# New_Multirotor_GPS_V1_2.net
KiCad netlist of a schematic drawn in EAGLE
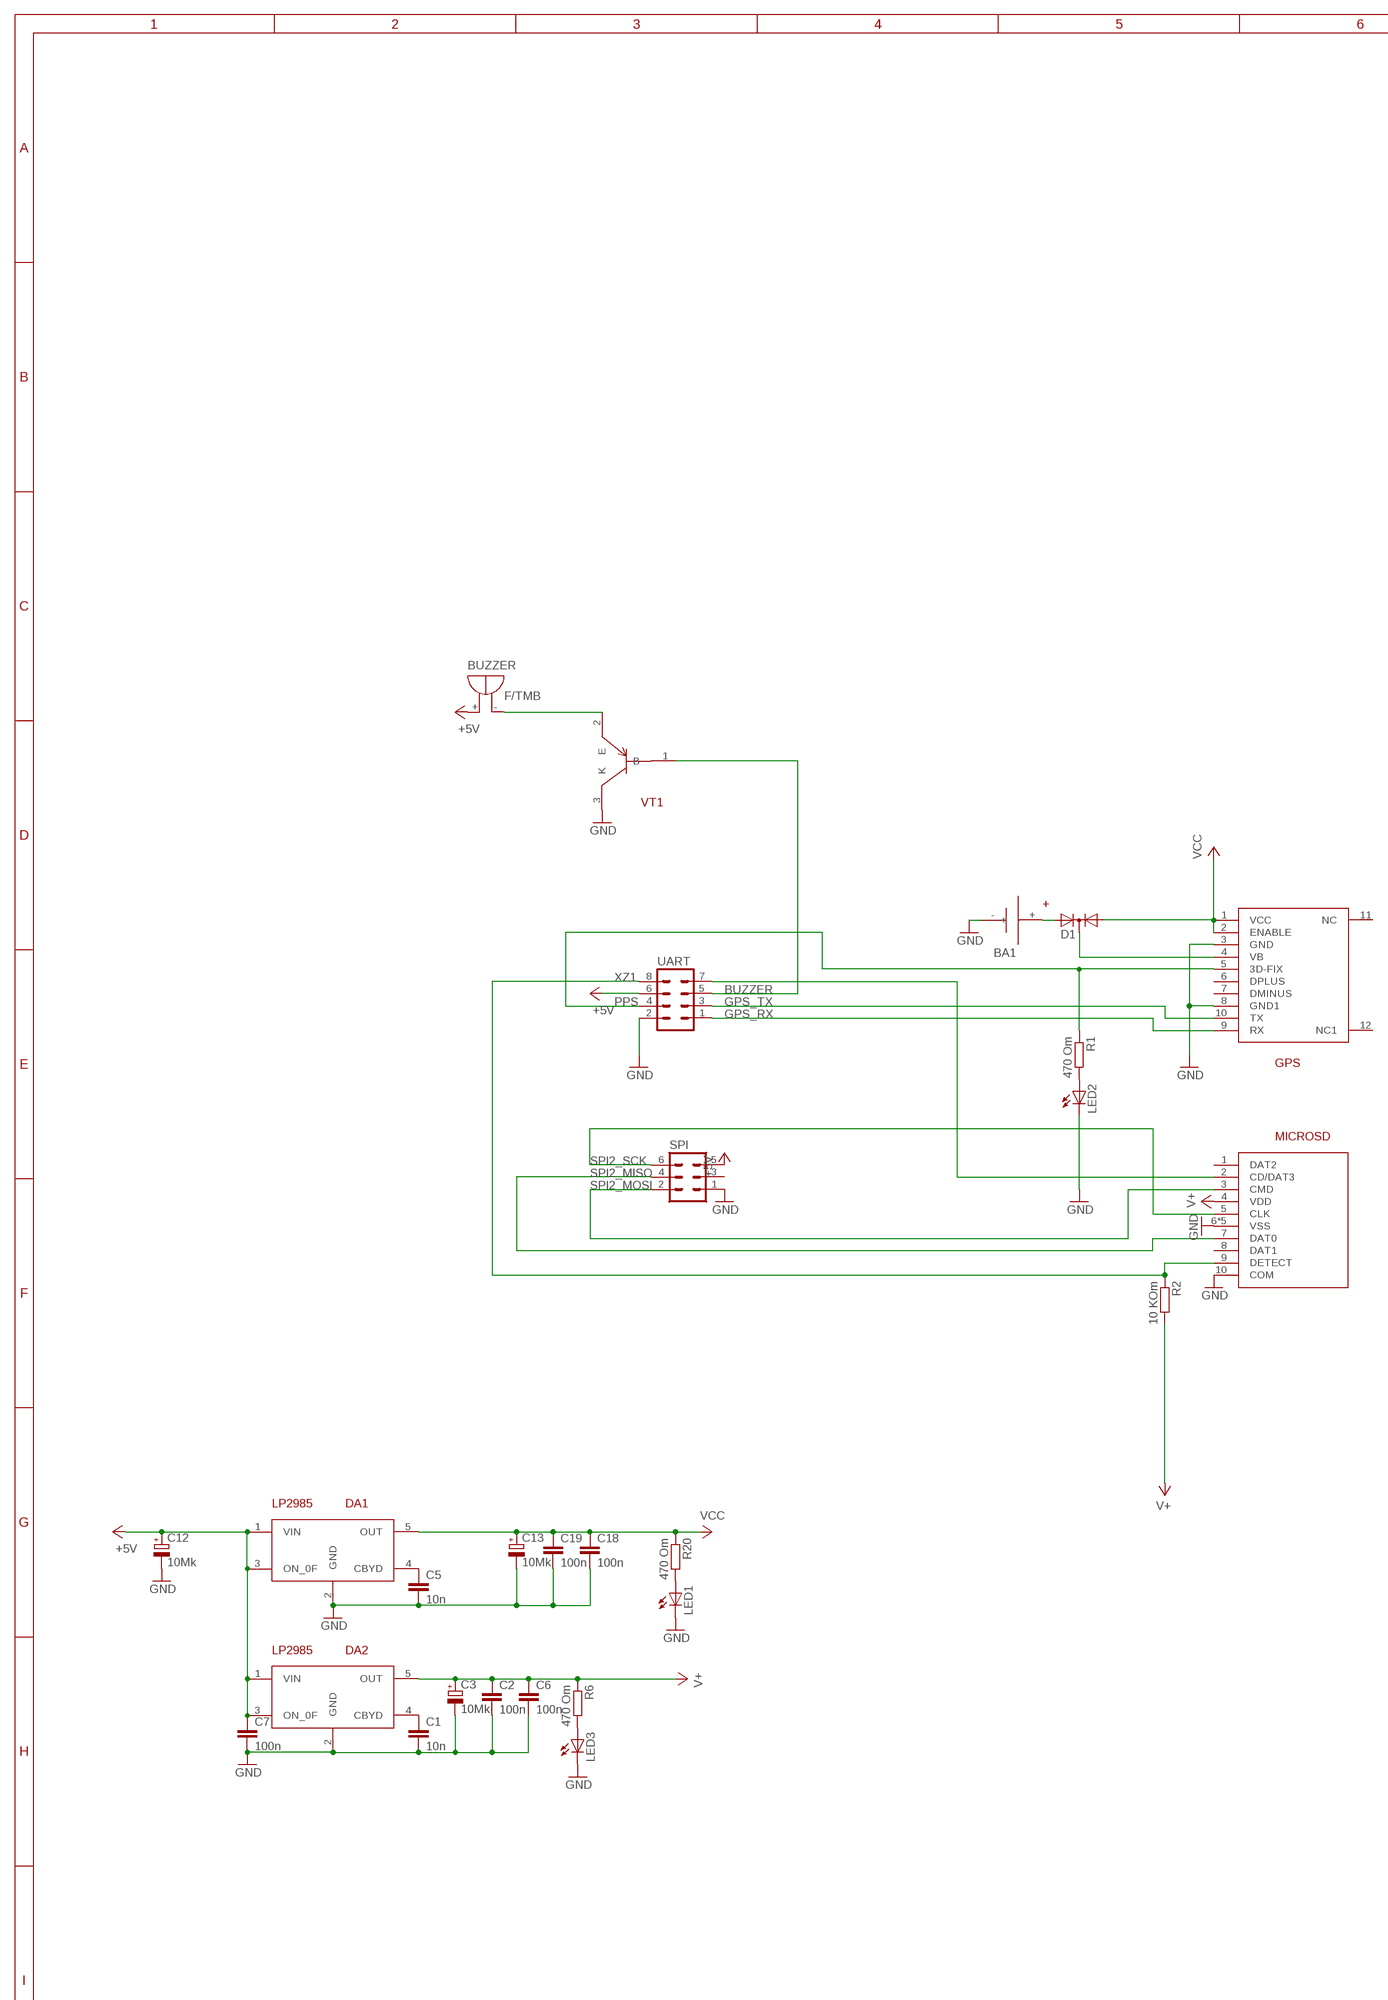
[diagram p0: schematic, sheet 1, part 1 of 2]
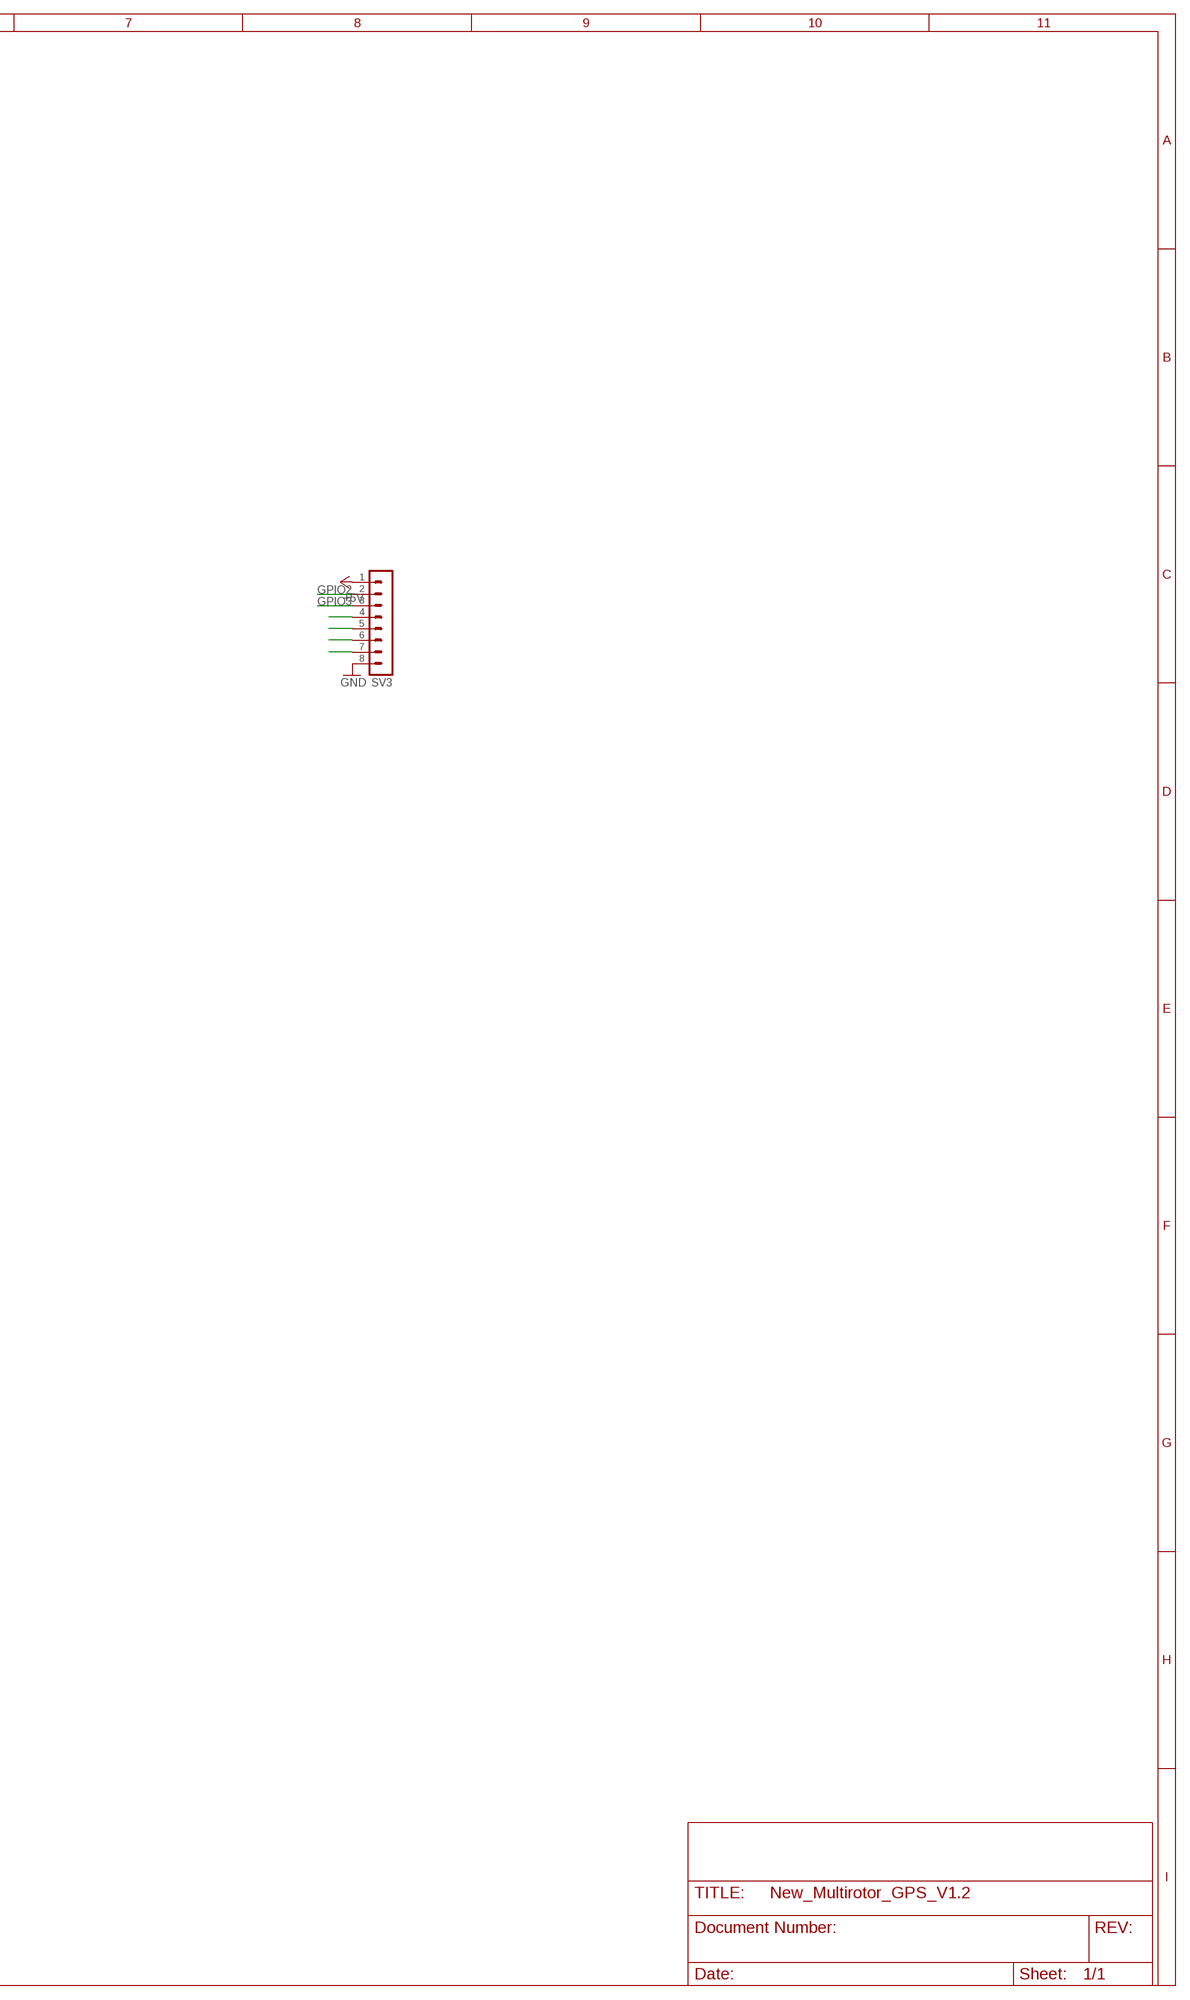
[diagram p1: schematic, sheet 1, part 2 of 2]

(export (version "E")
  (design (tool "Eeschema 10.0.6"))
  (components
    (comp (ref "BA1")
      (value "BAT")
      (footprint "eagle-import:BAT")
      (libsource (lib "eagle-import") (part "BAT"))
    )
    (comp (ref "BUZZER")
      (value "F/TMB")
      (footprint "eagle-import:F_TMB")
      (libsource (lib "eagle-import") (part "F/TMB"))
    )
    (comp (ref "C1")
      (value "10n")
      (footprint "eagle-import:C0603K")
      (libsource (lib "eagle-import") (part "C-EUC0603K"))
    )
    (comp (ref "C2")
      (value "100n")
      (footprint "eagle-import:C0603K")
      (libsource (lib "eagle-import") (part "C-EUC0603K"))
    )
    (comp (ref "C3")
      (value "10Mk")
      (footprint "eagle-import:A_3216-18W")
      (libsource (lib "eagle-import") (part "CPOL-EUA/3216-18W"))
    )
    (comp (ref "C5")
      (value "10n")
      (footprint "eagle-import:C0603K")
      (libsource (lib "eagle-import") (part "C-EUC0603K"))
    )
    (comp (ref "C6")
      (value "100n")
      (footprint "eagle-import:C0603K")
      (libsource (lib "eagle-import") (part "C-EUC0603K"))
    )
    (comp (ref "C7")
      (value "100n")
      (footprint "eagle-import:C0603K")
      (libsource (lib "eagle-import") (part "C-EUC0603K"))
    )
    (comp (ref "C12")
      (value "10Mk")
      (footprint "eagle-import:A_3216-18W")
      (libsource (lib "eagle-import") (part "CPOL-EUA/3216-18W"))
    )
    (comp (ref "C13")
      (value "10Mk")
      (footprint "eagle-import:A_3216-18W")
      (libsource (lib "eagle-import") (part "CPOL-EUA/3216-18W"))
    )
    (comp (ref "C18")
      (value "100n")
      (footprint "eagle-import:C0603K")
      (libsource (lib "eagle-import") (part "C-EUC0603K"))
    )
    (comp (ref "C19")
      (value "100n")
      (footprint "eagle-import:C0603K")
      (libsource (lib "eagle-import") (part "C-EUC0603K"))
    )
    (comp (ref "D1")
      (value "DIODE-2AC|CASOT23")
      (footprint "eagle-import:SOT23")
      (libsource (lib "eagle-import") (part "DIODE-2AC|CASOT23"))
    )
    (comp (ref "DA1")
      (value "LP2985")
      (footprint "eagle-import:SOT23-5L")
      (libsource (lib "eagle-import") (part "3.3"))
    )
    (comp (ref "DA2")
      (value "LP2985")
      (footprint "eagle-import:SOT23-5L")
      (libsource (lib "eagle-import") (part "3.3"))
    )
    (comp (ref "GPS")
      (value "FGPMMOPA6B")
      (footprint "eagle-import:FGPMMOPA6B")
      (libsource (lib "eagle-import") (part "FGPMMOPA6B"))
    )
    (comp (ref "LED1")
      (value "LEDCHIPLED_0603")
      (footprint "eagle-import:CHIPLED_0603")
      (libsource (lib "eagle-import") (part "LEDCHIPLED_0603"))
    )
    (comp (ref "LED2")
      (value "LEDCHIPLED_0603")
      (footprint "eagle-import:CHIPLED_0603")
      (libsource (lib "eagle-import") (part "LEDCHIPLED_0603"))
    )
    (comp (ref "LED3")
      (value "LEDCHIPLED_0603")
      (footprint "eagle-import:CHIPLED_0603")
      (libsource (lib "eagle-import") (part "LEDCHIPLED_0603"))
    )
    (comp (ref "MICROSD")
      (value "MICROCD_MAIN")
      (footprint "eagle-import:MICROSD_MAIN")
      (libsource (lib "eagle-import") (part "MICROCD_MAIN"))
    )
    (comp (ref "R1")
      (value "470 Om")
      (footprint "eagle-import:R0603")
      (libsource (lib "eagle-import") (part "R-EU_R0603"))
    )
    (comp (ref "R2")
      (value "10 KOm")
      (footprint "eagle-import:R0603")
      (libsource (lib "eagle-import") (part "R-EU_R0603"))
    )
    (comp (ref "R6")
      (value "470 Om")
      (footprint "eagle-import:R0603")
      (libsource (lib "eagle-import") (part "R-EU_R0603"))
    )
    (comp (ref "R20")
      (value "470 Om")
      (footprint "eagle-import:R0603")
      (libsource (lib "eagle-import") (part "R-EU_R0603"))
    )
    (comp (ref "SPI")
      (value "MA03-2")
      (footprint "eagle-import:MA03-2")
      (libsource (lib "eagle-import") (part "MA03-2"))
    )
    (comp (ref "SV3")
      (value "MA08-1")
      (footprint "eagle-import:MA08-1")
      (libsource (lib "eagle-import") (part "MA08-1"))
    )
    (comp (ref "UART")
      (value "MA04-2")
      (footprint "eagle-import:MA04-2")
      (libsource (lib "eagle-import") (part "MA04-2"))
    )
    (comp (ref "VT1")
      (value "MMBT3906")
      (footprint "eagle-import:SOT23B-3")
      (libsource (lib "eagle-import") (part "MMBT3906"))
    )
  )
  (nets
    (net (code "1") (name "+5V") (class "Default")
      (node (ref "BUZZER") (pin "+") (pinfunction "+_+") (pintype "passive"))
      (node (ref "C12") (pin "+") (pinfunction "+_+") (pintype "passive"))
      (node (ref "C7") (pin "1") (pinfunction "1_1") (pintype "passive"))
      (node (ref "DA1") (pin "1") (pinfunction "VIN_1") (pintype "bidirectional"))
      (node (ref "DA1") (pin "3") (pinfunction "ON_0F_3") (pintype "bidirectional"))
      (node (ref "DA2") (pin "1") (pinfunction "VIN_1") (pintype "bidirectional"))
      (node (ref "DA2") (pin "3") (pinfunction "ON_0F_3") (pintype "bidirectional"))
      (node (ref "SPI") (pin "5") (pinfunction "5_5") (pintype "passive"))
      (node (ref "SV3") (pin "1") (pinfunction "1_1") (pintype "passive"))
      (node (ref "UART") (pin "6") (pinfunction "6_6") (pintype "passive"))
    )
    (net (code "2") (name "/BUZZER") (class "Default")
      (node (ref "UART") (pin "5") (pinfunction "5_5") (pintype "passive"))
      (node (ref "VT1") (pin "1") (pinfunction "B_1") (pintype "bidirectional"))
    )
    (net (code "3") (name "/GPIO2") (class "Default")
      (node (ref "SV3") (pin "2") (pinfunction "2_2") (pintype "passive"))
    )
    (net (code "4") (name "/GPIO3") (class "Default")
      (node (ref "SV3") (pin "3") (pinfunction "3_3") (pintype "passive"))
    )
    (net (code "5") (name "/GPS_RX") (class "Default")
      (node (ref "GPS") (pin "9") (pinfunction "RX_9") (pintype "bidirectional"))
      (node (ref "UART") (pin "1") (pinfunction "1_1") (pintype "passive"))
    )
    (net (code "6") (name "/GPS_TX") (class "Default")
      (node (ref "GPS") (pin "10") (pinfunction "TX_10") (pintype "bidirectional"))
      (node (ref "UART") (pin "3") (pinfunction "3_3") (pintype "passive"))
    )
    (net (code "7") (name "/PPS") (class "Default")
      (node (ref "GPS") (pin "5") (pinfunction "3D-FIX_5") (pintype "bidirectional"))
      (node (ref "R1") (pin "1") (pinfunction "1_1") (pintype "passive"))
      (node (ref "UART") (pin "4") (pinfunction "4_4") (pintype "passive"))
    )
    (net (code "8") (name "/SPI2_MISO") (class "Default")
      (node (ref "MICROSD") (pin "7") (pinfunction "DAT0_7") (pintype "bidirectional"))
      (node (ref "SPI") (pin "4") (pinfunction "4_4") (pintype "passive"))
    )
    (net (code "9") (name "/SPI2_MOSI") (class "Default")
      (node (ref "MICROSD") (pin "3") (pinfunction "CMD_3") (pintype "bidirectional"))
      (node (ref "SPI") (pin "2") (pinfunction "2_2") (pintype "passive"))
    )
    (net (code "10") (name "/SPI2_SCK") (class "Default")
      (node (ref "MICROSD") (pin "5") (pinfunction "CLK_5") (pintype "bidirectional"))
      (node (ref "SPI") (pin "6") (pinfunction "6_6") (pintype "passive"))
    )
    (net (code "11") (name "/XZ1") (class "Default")
      (node (ref "MICROSD") (pin "9") (pinfunction "DETECT_9") (pintype "bidirectional"))
      (node (ref "R2") (pin "1") (pinfunction "1_1") (pintype "passive"))
      (node (ref "UART") (pin "8") (pinfunction "8_8") (pintype "passive"))
    )
    (net (code "12") (name "GND") (class "Default")
      (node (ref "BA1") (pin "-") (pinfunction "-_-") (pintype "power_in"))
      (node (ref "C1") (pin "2") (pinfunction "2_2") (pintype "passive"))
      (node (ref "C12") (pin "-") (pinfunction "-_-") (pintype "passive"))
      (node (ref "C13") (pin "-") (pinfunction "-_-") (pintype "passive"))
      (node (ref "C18") (pin "2") (pinfunction "2_2") (pintype "passive"))
      (node (ref "C19") (pin "2") (pinfunction "2_2") (pintype "passive"))
      (node (ref "C2") (pin "2") (pinfunction "2_2") (pintype "passive"))
      (node (ref "C3") (pin "-") (pinfunction "-_-") (pintype "passive"))
      (node (ref "C5") (pin "2") (pinfunction "2_2") (pintype "passive"))
      (node (ref "C6") (pin "2") (pinfunction "2_2") (pintype "passive"))
      (node (ref "C7") (pin "2") (pinfunction "2_2") (pintype "passive"))
      (node (ref "DA1") (pin "2") (pinfunction "GND_2") (pintype "bidirectional"))
      (node (ref "DA2") (pin "2") (pinfunction "GND_2") (pintype "bidirectional"))
      (node (ref "GPS") (pin "3") (pinfunction "GND_3") (pintype "bidirectional"))
      (node (ref "GPS") (pin "8") (pinfunction "GND1_8") (pintype "bidirectional"))
      (node (ref "LED1") (pin "C") (pinfunction "C_C") (pintype "passive"))
      (node (ref "LED2") (pin "C") (pinfunction "C_C") (pintype "passive"))
      (node (ref "LED3") (pin "C") (pinfunction "C_C") (pintype "passive"))
      (node (ref "MICROSD") (pin "10") (pinfunction "COM_10") (pintype "bidirectional"))
      (node (ref "MICROSD") (pin "11") (pinfunction "VSS_11") (pintype "bidirectional"))
      (node (ref "MICROSD") (pin "12") (pinfunction "VSS_12") (pintype "bidirectional"))
      (node (ref "MICROSD") (pin "13") (pinfunction "VSS_13") (pintype "bidirectional"))
      (node (ref "MICROSD") (pin "14") (pinfunction "VSS_14") (pintype "bidirectional"))
      (node (ref "MICROSD") (pin "6") (pinfunction "VSS_6") (pintype "bidirectional"))
      (node (ref "SPI") (pin "1") (pinfunction "1_1") (pintype "passive"))
      (node (ref "SV3") (pin "8") (pinfunction "8_8") (pintype "passive"))
      (node (ref "UART") (pin "2") (pinfunction "2_2") (pintype "passive"))
      (node (ref "VT1") (pin "3") (pinfunction "K_3") (pintype "bidirectional"))
    )
    (net (code "13") (name "Net-(D1-A2)") (class "Default")
      (node (ref "BA1") (pin "+") (pinfunction "+_+") (pintype "power_in"))
      (node (ref "D1") (pin "2") (pinfunction "A2_2") (pintype "passive"))
    )
    (net (code "14") (name "Net-(D1-C)") (class "Default")
      (node (ref "D1") (pin "3") (pinfunction "C_3") (pintype "passive"))
      (node (ref "GPS") (pin "4") (pinfunction "VB_4") (pintype "bidirectional"))
    )
    (net (code "15") (name "Net-(DA1-CBYD)") (class "Default")
      (node (ref "C5") (pin "1") (pinfunction "1_1") (pintype "passive"))
      (node (ref "DA1") (pin "4") (pinfunction "CBYD_4") (pintype "bidirectional"))
    )
    (net (code "16") (name "Net-(DA2-CBYD)") (class "Default")
      (node (ref "C1") (pin "1") (pinfunction "1_1") (pintype "passive"))
      (node (ref "DA2") (pin "4") (pinfunction "CBYD_4") (pintype "bidirectional"))
    )
    (net (code "17") (name "Net-(LED1-PadA)") (class "Default")
      (node (ref "LED1") (pin "A") (pinfunction "A_A") (pintype "passive"))
      (node (ref "R20") (pin "2") (pinfunction "2_2") (pintype "passive"))
    )
    (net (code "18") (name "Net-(LED2-PadA)") (class "Default")
      (node (ref "LED2") (pin "A") (pinfunction "A_A") (pintype "passive"))
      (node (ref "R1") (pin "2") (pinfunction "2_2") (pintype "passive"))
    )
    (net (code "19") (name "Net-(LED3-PadA)") (class "Default")
      (node (ref "LED3") (pin "A") (pinfunction "A_A") (pintype "passive"))
      (node (ref "R6") (pin "2") (pinfunction "2_2") (pintype "passive"))
    )
    (net (code "20") (name "Net-(MICROSD-CD{slash}DAT3)") (class "Default")
      (node (ref "MICROSD") (pin "2") (pinfunction "CD/DAT3_2") (pintype "bidirectional"))
      (node (ref "UART") (pin "7") (pinfunction "7_7") (pintype "passive"))
    )
    (net (code "21") (name "Net-(VT1-E)") (class "Default")
      (node (ref "BUZZER") (pin "-") (pinfunction "-_-") (pintype "passive"))
      (node (ref "VT1") (pin "2") (pinfunction "E_2") (pintype "bidirectional"))
    )
    (net (code "22") (name "V+") (class "Default")
      (node (ref "C2") (pin "1") (pinfunction "1_1") (pintype "passive"))
      (node (ref "C3") (pin "+") (pinfunction "+_+") (pintype "passive"))
      (node (ref "C6") (pin "1") (pinfunction "1_1") (pintype "passive"))
      (node (ref "DA2") (pin "5") (pinfunction "OUT_5") (pintype "bidirectional"))
      (node (ref "MICROSD") (pin "4") (pinfunction "VDD_4") (pintype "bidirectional"))
      (node (ref "R2") (pin "2") (pinfunction "2_2") (pintype "passive"))
      (node (ref "R6") (pin "1") (pinfunction "1_1") (pintype "passive"))
    )
    (net (code "23") (name "VCC") (class "Default")
      (node (ref "C13") (pin "+") (pinfunction "+_+") (pintype "passive"))
      (node (ref "C18") (pin "1") (pinfunction "1_1") (pintype "passive"))
      (node (ref "C19") (pin "1") (pinfunction "1_1") (pintype "passive"))
      (node (ref "D1") (pin "1") (pinfunction "A1_1") (pintype "passive"))
      (node (ref "DA1") (pin "5") (pinfunction "OUT_5") (pintype "bidirectional"))
      (node (ref "GPS") (pin "1") (pinfunction "VCC_1") (pintype "bidirectional"))
      (node (ref "GPS") (pin "2") (pinfunction "ENABLE_2") (pintype "bidirectional"))
      (node (ref "R20") (pin "1") (pinfunction "1_1") (pintype "passive"))
    )
    (net (code "24") (name "unconnected-(GPS-DMINUS-Pad7)") (class "Default")
      (node (ref "GPS") (pin "7") (pinfunction "DMINUS_7") (pintype "bidirectional"))
    )
    (net (code "25") (name "unconnected-(GPS-DPLUS-Pad6)") (class "Default")
      (node (ref "GPS") (pin "6") (pinfunction "DPLUS_6") (pintype "bidirectional"))
    )
    (net (code "26") (name "unconnected-(GPS-NC-Pad11)") (class "Default")
      (node (ref "GPS") (pin "11") (pinfunction "NC_11") (pintype "bidirectional"))
    )
    (net (code "27") (name "unconnected-(GPS-NC1-Pad12)") (class "Default")
      (node (ref "GPS") (pin "12") (pinfunction "NC1_12") (pintype "bidirectional"))
    )
    (net (code "28") (name "unconnected-(MICROSD-DAT1-Pad8)") (class "Default")
      (node (ref "MICROSD") (pin "8") (pinfunction "DAT1_8") (pintype "bidirectional"))
    )
    (net (code "29") (name "unconnected-(MICROSD-DAT2-Pad1)") (class "Default")
      (node (ref "MICROSD") (pin "1") (pinfunction "DAT2_1") (pintype "bidirectional"))
    )
    (net (code "30") (name "unconnected-(SPI-Pad3)") (class "Default")
      (node (ref "SPI") (pin "3") (pinfunction "3_3") (pintype "passive"))
    )
    (net (code "31") (name "unconnected-(SV3-Pad4)") (class "Default")
      (node (ref "SV3") (pin "4") (pinfunction "4_4") (pintype "passive"))
    )
    (net (code "32") (name "unconnected-(SV3-Pad5)") (class "Default")
      (node (ref "SV3") (pin "5") (pinfunction "5_5") (pintype "passive"))
    )
    (net (code "33") (name "unconnected-(SV3-Pad6)") (class "Default")
      (node (ref "SV3") (pin "6") (pinfunction "6_6") (pintype "passive"))
    )
    (net (code "34") (name "unconnected-(SV3-Pad7)") (class "Default")
      (node (ref "SV3") (pin "7") (pinfunction "7_7") (pintype "passive"))
    )
  )
)
